# 5V-Reg.net
KiCad netlist of a schematic drawn in Altium Designer
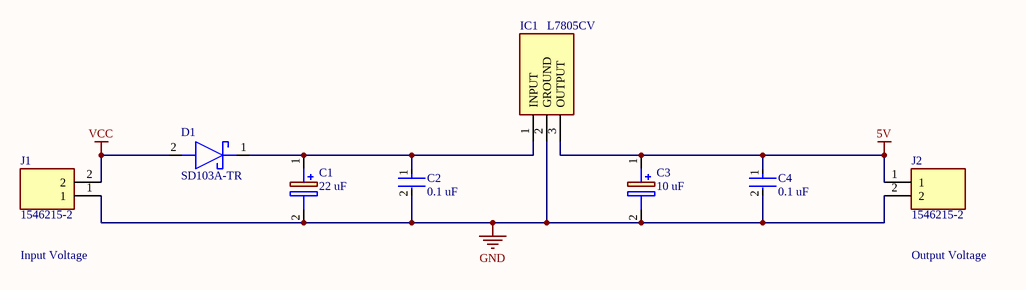
[diagram p0: 5V-Reg.SchDoc]

(export (version "E")
  (design (tool "Eeschema 10.0.6"))
  (components
    (comp (ref "C1")
      (value "22 uF")
      (footprint "SamacSys:CAPPRD200W52D500H1250")
      (description "Capacitor Polarised")
      (fields
        (field (name "MANUFACTURER_PART_NUMBER") "860010772002")
        (field (name "MOUSER PART NUMBER") "710-860010772002")
      )
      (libsource (lib "*") (part "860010772002"))
    )
    (comp (ref "C2")
      (value "0.1 uF")
      (footprint "FP-RDE0P1-MFG")
      (description "Ceramic Capacitor 100nF ±10% 25V X7R Radial")
      (fields (field (name "TOLERANCE") "10%"))
      (libsource (lib "Altium Content Vault") (part "b4654b650e69147ec39a6b967a45e02"))
    )
    (comp (ref "C3")
      (value "10 uF")
      (footprint "SamacSys:CAPPRD200W55D500H1250")
      (description "Capacitor Polarised")
      (fields
        (field (name "MANUFACTURER_PART_NUMBER") "EEU-FR1H100")
        (field (name "MOUSER PART NUMBER") "667-EEU-FR1H100")
      )
      (libsource (lib "*") (part "EEU-FR1H100"))
    )
    (comp (ref "C4")
      (value "0.1 uF")
      (footprint "FP-RDE0P1-MFG")
      (description "Ceramic Capacitor 100nF ±10% 25V X7R Radial")
      (fields (field (name "TOLERANCE") "10%"))
      (libsource (lib "Altium Content Vault") (part "b4654b650e69147ec39a6b967a45e02"))
    )
    (comp (ref "D1")
      (value "SD103A-TR")
      (footprint "SamacSys:DIOAD950W60L350D150")
      (description "Schottky Diode")
      (fields (field (name "MOUSER PART NUMBER") "625-SD103A"))
      (libsource (lib "*") (part "SD103A-TR"))
    )
    (comp (ref "IC1")
      (value "L7805CV")
      (footprint "SamacSys:TO255P460X1020X2008-3P")
      (description "Integrated Circuit")
      (fields (field (name "MOUSER PART NUMBER") "511-L7805CV"))
      (libsource (lib "*") (part "L7805CV"))
    )
    (comp (ref "J1")
      (value "1546215-2")
      (footprint "SamacSys:15462152")
      (description "Connector")
      (fields (field (name "MOUSER PART NUMBER") "571-1546215-2"))
      (libsource (lib "*") (part "1546215-2"))
    )
    (comp (ref "J2")
      (value "1546215-2")
      (footprint "SamacSys:15462152")
      (description "Connector")
      (fields (field (name "MOUSER PART NUMBER") "571-1546215-2"))
      (libsource (lib "") (part "1546215-2_1"))
    )
  )
  (nets
    (net (code "1") (name "5V") (class "Default")
      (node (ref "C3") (pin "1") (pinfunction "+_1") (pintype "power_in"))
      (node (ref "C4") (pin "1") (pinfunction "1_1") (pintype "passive"))
      (node (ref "IC1") (pin "3") (pinfunction "OUTPUT_3") (pintype "passive"))
      (node (ref "J2") (pin "1") (pinfunction "1_1") (pintype "passive"))
    )
    (net (code "2") (name "GND") (class "Default")
      (node (ref "C1") (pin "2") (pinfunction "-_2") (pintype "passive"))
      (node (ref "C2") (pin "2") (pinfunction "2_2") (pintype "passive"))
      (node (ref "C3") (pin "2") (pinfunction "-_2") (pintype "power_in"))
      (node (ref "C4") (pin "2") (pinfunction "2_2") (pintype "passive"))
      (node (ref "IC1") (pin "2") (pinfunction "GROUND_2") (pintype "passive"))
      (node (ref "J1") (pin "1") (pinfunction "1_1") (pintype "passive"))
      (node (ref "J2") (pin "2") (pinfunction "2_2") (pintype "passive"))
    )
    (net (code "3") (name "Net-(C1-+)") (class "Default")
      (node (ref "C1") (pin "1") (pinfunction "+_1") (pintype "passive"))
      (node (ref "C2") (pin "1") (pinfunction "1_1") (pintype "passive"))
      (node (ref "D1") (pin "1") (pinfunction "K_1") (pintype "passive"))
      (node (ref "IC1") (pin "1") (pinfunction "INPUT_1") (pintype "passive"))
    )
    (net (code "4") (name "VCC") (class "Default")
      (node (ref "D1") (pin "2") (pinfunction "A_2") (pintype "passive"))
      (node (ref "J1") (pin "2") (pinfunction "2_2") (pintype "passive"))
    )
  )
)
